# Dribble.net
KiCad netlist of a schematic drawn in Altium Designer
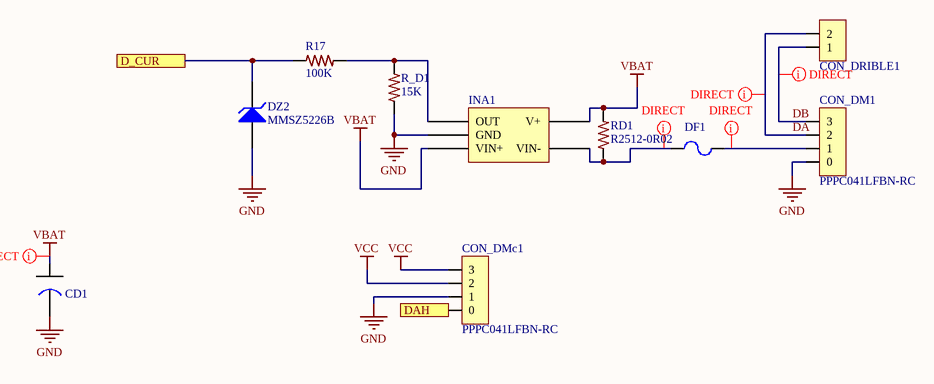
[diagram p0: Dribble.SchDoc]

(export (version "E")
  (design (tool "Eeschema 10.0.6"))
  (components
    (comp (ref "CD1")
      (value "EEE-FK1C681GP")
      (footprint "EEE-FK1C681GP")
      (description "Aluminum Electrolytic Capacitors - SMD Al Lytic Cap SMT FK Series 105C")
      (libsource (lib "Schlib1") (part "CAP AL 680UF/16V"))
    )
    (comp (ref "CON_DM1")
      (value "PPPC041LFBN-RC")
      (footprint "04x01_Conector_Female - duplicate")
      (description "4 Position Header Connector 0.100\" (2.54mm) Through Hole Gold")
      (libsource (lib "Schlib1") (part "04x01_Conector_Female-SCH"))
    )
    (comp (ref "CON_DMc1")
      (value "PPPC041LFBN-RC")
      (footprint "04x01_Conector_Female - duplicate")
      (description "4 Position Header Connector 0.100\" (2.54mm) Through Hole Gold")
      (libsource (lib "Schlib1") (part "04x01_Conector_Female-SCH"))
    )
    (comp (ref "CON_DRIBLE1")
      (value "0022112022")
      (footprint "02x01_Conector_Male")
      (description "CONN HEADER 2POS .100 VERT GOLD")
      (libsource (lib "Schlib1") (part "02x01_Conector_Male"))
    )
    (comp (ref "DF1")
      (value "MF-MSMF250/16X")
      (footprint "RESC4632X16N")
      (description "PTC RESETTABLE .30A 30V 1812")
      (libsource (lib "IMBEL") (part "MF-MSMF250/16X-01.A.1"))
    )
    (comp (ref "DZ2")
      (value "MMSZ5226B")
      (footprint "FAIR-SOD-123-2_V")
      (description "Zener Diode, 3.3 V, -55 to 150 degC, 2-Pin SOD-123，RoHS, Tape and Reel")
      (fields (field (name "MANUFACTURER") "FairchildSemiconductor"))
      (libsource (lib "Altium Content Vault") (part "DZEN-AK-2"))
    )
    (comp (ref "INA1")
      (value "INA169NA")
      (footprint "SOT95P280X125-5N")
      (description "IC CURRENT MONITOR 0.5% SOT23-5")
      (libsource (lib "IMBEL") (part "ina169"))
    )
    (comp (ref "R17")
      (value "100K")
      (footprint "0402-RES-HD")
      (description "RES 1K OHM 1/10W 1% 0402 SMD")
      (fields (field (name "PART NO") "ERJ-2RKF1001X"))
      (libsource (lib "IMBEL") (part "RESISTOR"))
    )
    (comp (ref "RD1")
      (value "R2512-0R02")
      (footprint "2512-RES-HD")
      (description "RES .02 OHM 2W 1% 2512 SMD")
      (fields (field (name "PART NO") "WSL2512R0200FEA18"))
      (libsource (lib "IMBEL") (part "R2512-0R02-4"))
    )
    (comp (ref "R_D1")
      (value "15K")
      (footprint "0402-RES-HD")
      (description "RES 1K OHM 1/10W 1% 0402 SMD")
      (fields (field (name "PART NO") "ERJ-2RKF1001X"))
      (libsource (lib "IMBEL") (part "RESISTOR"))
    )
  )
  (nets
    (net (code "1") (name "/DA") (class "Default")
      (node (ref "CON_DM1") (pin "2") (pinfunction "2_2") (pintype "passive"))
      (node (ref "CON_DRIBLE1") (pin "2") (pinfunction "2_2") (pintype "passive"))
    )
    (net (code "2") (name "/DAH") (class "Default")
      (node (ref "CON_DMc1") (pin "0") (pinfunction "0_0") (pintype "passive"))
    )
    (net (code "3") (name "/DB") (class "Default")
      (node (ref "CON_DM1") (pin "3") (pinfunction "3_3") (pintype "passive"))
      (node (ref "CON_DRIBLE1") (pin "1") (pinfunction "1_1") (pintype "passive"))
    )
    (net (code "4") (name "/D_CUR") (class "Default")
      (node (ref "DZ2") (pin "2") (pinfunction "K_2") (pintype "passive"))
      (node (ref "R17") (pin "2") (pinfunction "2_2") (pintype "passive"))
    )
    (net (code "5") (name "GND") (class "Default")
      (node (ref "CD1") (pin "2") (pinfunction "2_2") (pintype "passive"))
      (node (ref "CON_DM1") (pin "0") (pinfunction "0_0") (pintype "passive"))
      (node (ref "CON_DMc1") (pin "1") (pinfunction "1_1") (pintype "passive"))
      (node (ref "DZ2") (pin "1") (pinfunction "A_1") (pintype "passive"))
      (node (ref "INA1") (pin "2") (pinfunction "GND_2") (pintype "passive"))
      (node (ref "R_D1") (pin "1") (pinfunction "1_1") (pintype "passive"))
    )
    (net (code "6") (name "Net-(CON_DM1-Pad1)") (class "Default")
      (node (ref "CON_DM1") (pin "1") (pinfunction "1_1") (pintype "passive"))
      (node (ref "DF1") (pin "1") (pinfunction "1_1") (pintype "passive"))
    )
    (net (code "7") (name "Net-(INA1-OUT)") (class "Default")
      (node (ref "INA1") (pin "1") (pinfunction "OUT_1") (pintype "passive"))
      (node (ref "R17") (pin "1") (pinfunction "1_1") (pintype "passive"))
      (node (ref "R_D1") (pin "2") (pinfunction "2_2") (pintype "passive"))
    )
    (net (code "8") (name "Net-(INA1-VIN-)") (class "Default")
      (node (ref "DF1") (pin "2") (pinfunction "2_2") (pintype "passive"))
      (node (ref "INA1") (pin "5") (pinfunction "VIN-_5") (pintype "passive"))
      (node (ref "RD1") (pin "1") (pinfunction "1_1") (pintype "passive"))
    )
    (net (code "9") (name "VBAT") (class "Default")
      (node (ref "CD1") (pin "1") (pinfunction "1_1") (pintype "passive"))
      (node (ref "INA1") (pin "3") (pinfunction "VIN+_3") (pintype "passive"))
      (node (ref "INA1") (pin "4") (pinfunction "V+_4") (pintype "passive"))
      (node (ref "RD1") (pin "2") (pinfunction "2_2") (pintype "passive"))
    )
    (net (code "10") (name "VCC") (class "Default")
      (node (ref "CON_DMc1") (pin "2") (pinfunction "2_2") (pintype "passive"))
      (node (ref "CON_DMc1") (pin "3") (pinfunction "3_3") (pintype "passive"))
    )
  )
)
